# hall.net
KiCad netlist of a schematic drawn in Altium Designer
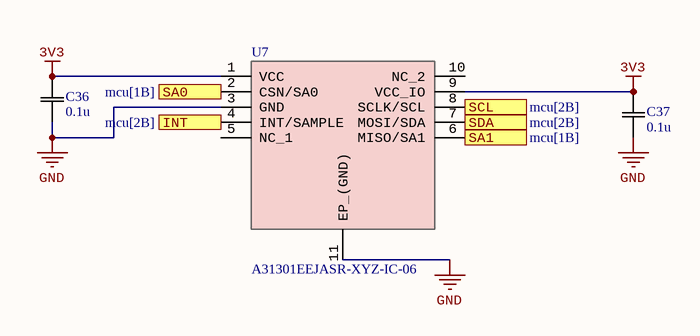
[diagram p0: hall.SchDoc]

(export (version "E")
  (design (tool "Eeschema 10.0.6"))
  (components
    (comp (ref "C36")
      (value "0.1u")
      (footprint "CAP_CC0201_YAG")
      (description "Description")
      (fields
        (field (name "MANUFACTURER_PART_NUMBER") "CC0201KRX5R7BB104")
        (field (name "COPYRIGHT") "Copyright (C) 2025 Ultra Librarian. All rights reserved.")
      )
      (libsource (lib "Ben Cheng") (part "CC0201KRX5R7BB104"))
    )
    (comp (ref "C37")
      (value "0.1u")
      (footprint "CAP_CC0201_YAG")
      (description "Description")
      (fields
        (field (name "MANUFACTURER_PART_NUMBER") "CC0201KRX5R7BB104")
        (field (name "COPYRIGHT") "Copyright (C) 2025 Ultra Librarian. All rights reserved.")
      )
      (libsource (lib "Ben Cheng") (part "CC0201KRX5R7BB104"))
    )
    (comp (ref "U7")
      (value "A31301EEJASR-XYZ-IC-06")
      (footprint "SON50P300X300X80-11N-D:SON50P300X300X80-11N-D")
      (description "3D Linear Hall-Effect Sensor with SPI, I2C Interfaces, and Advanced Low-Power Management")
      (fields (field (name "MOUSER PART NUMBER") "250-A31301EEJASRIC06"))
      (libsource (lib "A31301EEJASR-XYZ-IC-06") (part "A31301EEJASR-XYZ-IC-06"))
    )
  )
  (nets
    (net (code "1") (name "/INT") (class "Default")
      (node (ref "U7") (pin "4") (pinfunction "INT/SAMPLE_4") (pintype "passive"))
    )
    (net (code "2") (name "/SA0") (class "Default")
      (node (ref "U7") (pin "2") (pinfunction "CSN/SA0_2") (pintype "passive"))
    )
    (net (code "3") (name "/SA1") (class "Default")
      (node (ref "U7") (pin "6") (pinfunction "MISO/SA1_6") (pintype "passive"))
    )
    (net (code "4") (name "/SCL") (class "Default")
      (node (ref "U7") (pin "8") (pinfunction "SCLK/SCL_8") (pintype "passive"))
    )
    (net (code "5") (name "/SDA") (class "Default")
      (node (ref "U7") (pin "7") (pinfunction "MOSI/SDA_7") (pintype "passive"))
    )
    (net (code "6") (name "3V3") (class "Default")
      (node (ref "C36") (pin "2") (pinfunction "2_2") (pintype "passive"))
      (node (ref "C37") (pin "2") (pinfunction "2_2") (pintype "passive"))
      (node (ref "U7") (pin "1") (pinfunction "VCC_1") (pintype "passive"))
      (node (ref "U7") (pin "9") (pinfunction "VCC_IO_9") (pintype "passive"))
    )
    (net (code "7") (name "GND") (class "Default")
      (node (ref "C36") (pin "1") (pinfunction "1_1") (pintype "passive"))
      (node (ref "C37") (pin "1") (pinfunction "1_1") (pintype "passive"))
      (node (ref "U7") (pin "11") (pinfunction "EP_(GND)_11") (pintype "passive"))
      (node (ref "U7") (pin "3") (pinfunction "GND_3") (pintype "passive"))
    )
    (net (code "8") (name "unconnected-(U7-NC_1-Pad5)") (class "Default")
      (node (ref "U7") (pin "5") (pinfunction "NC_1_5") (pintype "passive"))
    )
    (net (code "9") (name "unconnected-(U7-NC_2-Pad10)") (class "Default")
      (node (ref "U7") (pin "10") (pinfunction "NC_2_10") (pintype "passive"))
    )
  )
)
